# placa_v4.net
KiCad netlist of a schematic drawn in EAGLE
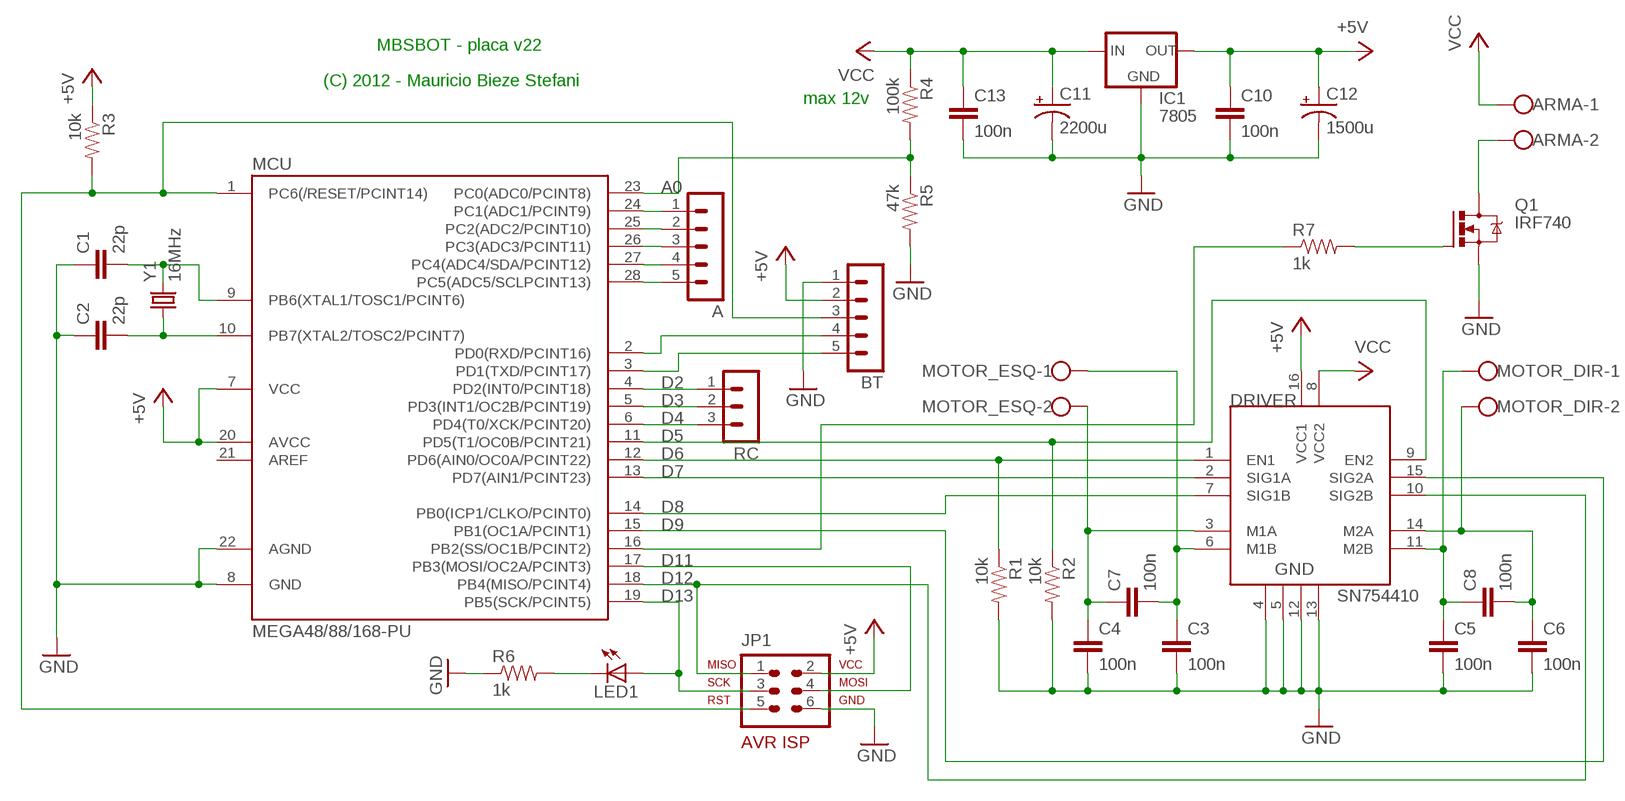
[diagram p0: schematic, sheet 1]

(export (version "E")
  (design (tool "Eeschema 10.0.6"))
  (components
    (comp (ref "A")
      (value "MA05-1")
      (footprint "eagle-import:MA05-1")
      (libsource (lib "eagle-import") (part "MA05-1"))
    )
    (comp (ref "ARMA")
      (value "W237-102")
      (footprint "eagle-import:W237-102")
      (fields (field (name "MPN") "237-102"))
      (libsource (lib "eagle-import") (part "W237-102"))
    )
    (comp (ref "BT")
      (value "MA05-1")
      (footprint "eagle-import:MA05-1")
      (libsource (lib "eagle-import") (part "MA05-1"))
    )
    (comp (ref "C1")
      (value "22p")
      (footprint "eagle-import:CAP-PTH-SMALL-KIT")
      (libsource (lib "eagle-import") (part "CAPKIT"))
    )
    (comp (ref "C2")
      (value "22p")
      (footprint "eagle-import:CAP-PTH-SMALL-KIT")
      (libsource (lib "eagle-import") (part "CAPKIT"))
    )
    (comp (ref "C3")
      (value "100n")
      (footprint "eagle-import:CAP-PTH-5MM")
      (libsource (lib "eagle-import") (part "CAPPTH1"))
    )
    (comp (ref "C4")
      (value "100n")
      (footprint "eagle-import:CAP-PTH-5MM")
      (libsource (lib "eagle-import") (part "CAPPTH1"))
    )
    (comp (ref "C5")
      (value "100n")
      (footprint "eagle-import:CAP-PTH-5MM")
      (libsource (lib "eagle-import") (part "CAPPTH1"))
    )
    (comp (ref "C6")
      (value "100n")
      (footprint "eagle-import:CAP-PTH-5MM")
      (libsource (lib "eagle-import") (part "CAPPTH1"))
    )
    (comp (ref "C7")
      (value "100n")
      (footprint "eagle-import:CAP-PTH-5MM")
      (libsource (lib "eagle-import") (part "CAPPTH1"))
    )
    (comp (ref "C8")
      (value "100n")
      (footprint "eagle-import:CAP-PTH-5MM")
      (libsource (lib "eagle-import") (part "CAPPTH1"))
    )
    (comp (ref "C10")
      (value "100n")
      (footprint "eagle-import:CAP-PTH-5MM")
      (libsource (lib "eagle-import") (part "CAPPTH1"))
    )
    (comp (ref "C11")
      (value "2200u")
      (footprint "eagle-import:CPOL-RADIAL-100UF-25V")
      (libsource (lib "eagle-import") (part "CAP_POLPTH1"))
    )
    (comp (ref "C12")
      (value "1500u")
      (footprint "eagle-import:CPOL-RADIAL-100UF-25V")
      (libsource (lib "eagle-import") (part "CAP_POLPTH1"))
    )
    (comp (ref "C13")
      (value "100n")
      (footprint "eagle-import:CAP-PTH-5MM")
      (libsource (lib "eagle-import") (part "CAPPTH1"))
    )
    (comp (ref "DRIVER")
      (value "SN754410")
      (footprint "eagle-import:DIP16")
      (libsource (lib "eagle-import") (part "SN754410"))
    )
    (comp (ref "IC1")
      (value "7805")
      (footprint "eagle-import:78XXS")
      (libsource (lib "eagle-import") (part "78XXS"))
    )
    (comp (ref "JP1")
      (value "AVR-ISP-6VERT")
      (footprint "eagle-import:AVR-ISP-6")
      (libsource (lib "eagle-import") (part "AVR-ISP-6VERT"))
    )
    (comp (ref "LED1")
      (value "LED3MM")
      (footprint "eagle-import:LED3MM")
      (libsource (lib "eagle-import") (part "LED3MM"))
    )
    (comp (ref "MCU")
      (value "MEGA48/88/168-PU")
      (footprint "eagle-import:DIL28-3")
      (libsource (lib "eagle-import") (part "MEGA48/88/168-PU"))
    )
    (comp (ref "MOTOR_DIR")
      (value "W237-102")
      (footprint "eagle-import:W237-102")
      (fields (field (name "MPN") "237-102"))
      (libsource (lib "eagle-import") (part "W237-102"))
    )
    (comp (ref "MOTOR_ESQ")
      (value "W237-102")
      (footprint "eagle-import:W237-102")
      (fields (field (name "MPN") "237-102"))
      (libsource (lib "eagle-import") (part "W237-102"))
    )
    (comp (ref "Q1")
      (value "IRF740")
      (footprint "eagle-import:TO220BV")
      (libsource (lib "eagle-import") (part "IRF740"))
    )
    (comp (ref "R1")
      (value "10k")
      (footprint "eagle-import:AXIAL-0.5")
      (libsource (lib "eagle-import") (part "RESISTORPTH-1/2W"))
    )
    (comp (ref "R2")
      (value "10k")
      (footprint "eagle-import:AXIAL-0.5")
      (libsource (lib "eagle-import") (part "RESISTORPTH-1/2W"))
    )
    (comp (ref "R3")
      (value "10k")
      (footprint "eagle-import:AXIAL-0.5")
      (libsource (lib "eagle-import") (part "RESISTORPTH-1/2W"))
    )
    (comp (ref "R4")
      (value "100k")
      (footprint "eagle-import:AXIAL-0.5")
      (libsource (lib "eagle-import") (part "RESISTORPTH-1/2W"))
    )
    (comp (ref "R5")
      (value "47k")
      (footprint "eagle-import:AXIAL-0.5")
      (libsource (lib "eagle-import") (part "RESISTORPTH-1/2W"))
    )
    (comp (ref "R6")
      (value "1k")
      (footprint "eagle-import:AXIAL-0.3-KIT")
      (libsource (lib "eagle-import") (part "RESISTORKIT"))
    )
    (comp (ref "R7")
      (value "1k")
      (footprint "eagle-import:AXIAL-0.3-KIT")
      (libsource (lib "eagle-import") (part "RESISTORKIT"))
    )
    (comp (ref "RC")
      (value "MA03-1")
      (footprint "eagle-import:MA03-1")
      (libsource (lib "eagle-import") (part "MA03-1"))
    )
    (comp (ref "Y1")
      (value "16MHz")
      (footprint "eagle-import:HC49US")
      (libsource (lib "eagle-import") (part "CRYSTALHC49US"))
    )
  )
  (nets
    (net (code "1") (name "+5V") (class "Default")
      (node (ref "BT") (pin "2") (pinfunction "2_2") (pintype "passive"))
      (node (ref "C10") (pin "1") (pinfunction "1_1") (pintype "passive"))
      (node (ref "C12") (pin "1") (pinfunction "+_1") (pintype "passive"))
      (node (ref "DRIVER") (pin "16") (pinfunction "VCC1_16") (pintype "power_in"))
      (node (ref "IC1") (pin "OUT") (pinfunction "OUT_OUT") (pintype "passive"))
      (node (ref "JP1") (pin "2") (pinfunction "2_2") (pintype "passive"))
      (node (ref "MCU") (pin "20") (pinfunction "AVCC_20") (pintype "passive"))
      (node (ref "MCU") (pin "7") (pinfunction "VCC_7") (pintype "power_in"))
      (node (ref "R3") (pin "P$1") (pinfunction "1_P$1") (pintype "passive"))
    )
    (net (code "2") (name "/A0") (class "Default")
      (node (ref "MCU") (pin "23") (pinfunction "PC0(ADC0/PCINT8)_23") (pintype "bidirectional"))
      (node (ref "R4") (pin "P$2") (pinfunction "2_P$2") (pintype "passive"))
      (node (ref "R5") (pin "P$1") (pinfunction "1_P$1") (pintype "passive"))
    )
    (net (code "3") (name "/D2") (class "Default")
      (node (ref "MCU") (pin "4") (pinfunction "PD2(INT0/PCINT18)_4") (pintype "bidirectional"))
      (node (ref "RC") (pin "1") (pinfunction "1_1") (pintype "passive"))
    )
    (net (code "4") (name "/D3") (class "Default")
      (node (ref "MCU") (pin "5") (pinfunction "PD3(INT1/OC2B/PCINT19)_5") (pintype "bidirectional"))
      (node (ref "RC") (pin "2") (pinfunction "2_2") (pintype "passive"))
    )
    (net (code "5") (name "/D4") (class "Default")
      (node (ref "MCU") (pin "6") (pinfunction "PD4(T0/XCK/PCINT20)_6") (pintype "bidirectional"))
      (node (ref "RC") (pin "3") (pinfunction "3_3") (pintype "passive"))
    )
    (net (code "6") (name "/D5") (class "Default")
      (node (ref "DRIVER") (pin "9") (pinfunction "EN2_9") (pintype "bidirectional"))
      (node (ref "MCU") (pin "11") (pinfunction "PD5(T1/OC0B/PCINT21)_11") (pintype "bidirectional"))
      (node (ref "R2") (pin "P$1") (pinfunction "1_P$1") (pintype "passive"))
    )
    (net (code "7") (name "/D6") (class "Default")
      (node (ref "DRIVER") (pin "1") (pinfunction "EN1_1") (pintype "bidirectional"))
      (node (ref "MCU") (pin "12") (pinfunction "PD6(AIN0/OC0A/PCINT22)_12") (pintype "bidirectional"))
      (node (ref "R1") (pin "P$1") (pinfunction "1_P$1") (pintype "passive"))
    )
    (net (code "8") (name "/D7") (class "Default")
      (node (ref "DRIVER") (pin "2") (pinfunction "SIG1A_2") (pintype "bidirectional"))
      (node (ref "MCU") (pin "13") (pinfunction "PD7(AIN1/PCINT23)_13") (pintype "bidirectional"))
    )
    (net (code "9") (name "/D8") (class "Default")
      (node (ref "DRIVER") (pin "7") (pinfunction "SIG1B_7") (pintype "bidirectional"))
      (node (ref "MCU") (pin "14") (pinfunction "PB0(ICP1/CLKO/PCINT0)_14") (pintype "bidirectional"))
    )
    (net (code "10") (name "/D9") (class "Default")
      (node (ref "DRIVER") (pin "15") (pinfunction "SIG2A_15") (pintype "bidirectional"))
      (node (ref "MCU") (pin "15") (pinfunction "PB1(OC1A/PCINT1)_15") (pintype "bidirectional"))
      (node (ref "MCU") (pin "16") (pinfunction "PB2(SS/OC1B/PCINT2)_16") (pintype "bidirectional"))
      (node (ref "R7") (pin "P$1") (pinfunction "1_P$1") (pintype "passive"))
    )
    (net (code "11") (name "/D11") (class "Default")
      (node (ref "JP1") (pin "4") (pinfunction "4_4") (pintype "passive"))
      (node (ref "MCU") (pin "17") (pinfunction "PB3(MOSI/OC2A/PCINT3)_17") (pintype "bidirectional"))
    )
    (net (code "12") (name "/D12") (class "Default")
      (node (ref "DRIVER") (pin "10") (pinfunction "SIG2B_10") (pintype "bidirectional"))
      (node (ref "JP1") (pin "1") (pinfunction "1_1") (pintype "passive"))
      (node (ref "MCU") (pin "18") (pinfunction "PB4(MISO/PCINT4)_18") (pintype "bidirectional"))
    )
    (net (code "13") (name "/D13") (class "Default")
      (node (ref "JP1") (pin "3") (pinfunction "3_3") (pintype "passive"))
      (node (ref "LED1") (pin "A") (pinfunction "A_A") (pintype "passive"))
      (node (ref "MCU") (pin "19") (pinfunction "PB5(SCK/PCINT5)_19") (pintype "bidirectional"))
    )
    (net (code "14") (name "GND") (class "Default")
      (node (ref "BT") (pin "1") (pinfunction "1_1") (pintype "passive"))
      (node (ref "C1") (pin "1") (pinfunction "1_1") (pintype "passive"))
      (node (ref "C10") (pin "2") (pinfunction "2_2") (pintype "passive"))
      (node (ref "C11") (pin "2") (pinfunction "-_2") (pintype "passive"))
      (node (ref "C12") (pin "2") (pinfunction "-_2") (pintype "passive"))
      (node (ref "C13") (pin "2") (pinfunction "2_2") (pintype "passive"))
      (node (ref "C2") (pin "1") (pinfunction "1_1") (pintype "passive"))
      (node (ref "C3") (pin "2") (pinfunction "2_2") (pintype "passive"))
      (node (ref "C4") (pin "2") (pinfunction "2_2") (pintype "passive"))
      (node (ref "C5") (pin "2") (pinfunction "2_2") (pintype "passive"))
      (node (ref "C6") (pin "2") (pinfunction "2_2") (pintype "passive"))
      (node (ref "DRIVER") (pin "12") (pinfunction "P12_12") (pintype "power_in"))
      (node (ref "DRIVER") (pin "13") (pinfunction "P13_13") (pintype "power_in"))
      (node (ref "DRIVER") (pin "4") (pinfunction "P4_4") (pintype "power_in"))
      (node (ref "DRIVER") (pin "5") (pinfunction "P5_5") (pintype "power_in"))
      (node (ref "IC1") (pin "GND") (pinfunction "GND_GND") (pintype "input"))
      (node (ref "JP1") (pin "6") (pinfunction "6_6") (pintype "passive"))
      (node (ref "MCU") (pin "22") (pinfunction "AGND_22") (pintype "power_in"))
      (node (ref "MCU") (pin "8") (pinfunction "GND_8") (pintype "power_in"))
      (node (ref "Q1") (pin "S") (pinfunction "S_S") (pintype "passive"))
      (node (ref "R1") (pin "P$2") (pinfunction "2_P$2") (pintype "passive"))
      (node (ref "R2") (pin "P$2") (pinfunction "2_P$2") (pintype "passive"))
      (node (ref "R5") (pin "P$2") (pinfunction "2_P$2") (pintype "passive"))
      (node (ref "R6") (pin "P$1") (pinfunction "1_P$1") (pintype "passive"))
    )
    (net (code "15") (name "Net-(ARMAB-KL)") (class "Default")
      (node (ref "ARMA") (pin "2") (pinfunction "KL_2") (pintype "passive"))
      (node (ref "Q1") (pin "D") (pinfunction "D_D") (pintype "passive"))
    )
    (net (code "16") (name "Net-(DRIVER-M1A)") (class "Default")
      (node (ref "C4") (pin "1") (pinfunction "1_1") (pintype "passive"))
      (node (ref "C7") (pin "1") (pinfunction "1_1") (pintype "passive"))
      (node (ref "DRIVER") (pin "3") (pinfunction "M1A_3") (pintype "bidirectional"))
      (node (ref "MOTOR_ESQ") (pin "2") (pinfunction "KL_2") (pintype "passive"))
    )
    (net (code "17") (name "Net-(DRIVER-M1B)") (class "Default")
      (node (ref "C3") (pin "1") (pinfunction "1_1") (pintype "passive"))
      (node (ref "C7") (pin "2") (pinfunction "2_2") (pintype "passive"))
      (node (ref "DRIVER") (pin "6") (pinfunction "M1B_6") (pintype "bidirectional"))
      (node (ref "MOTOR_ESQ") (pin "1") (pinfunction "KL_1") (pintype "passive"))
    )
    (net (code "18") (name "Net-(DRIVER-M2A)") (class "Default")
      (node (ref "C6") (pin "1") (pinfunction "1_1") (pintype "passive"))
      (node (ref "C8") (pin "2") (pinfunction "2_2") (pintype "passive"))
      (node (ref "DRIVER") (pin "14") (pinfunction "M2A_14") (pintype "bidirectional"))
      (node (ref "MOTOR_DIR") (pin "2") (pinfunction "KL_2") (pintype "passive"))
    )
    (net (code "19") (name "Net-(DRIVER-M2B)") (class "Default")
      (node (ref "C5") (pin "1") (pinfunction "1_1") (pintype "passive"))
      (node (ref "C8") (pin "1") (pinfunction "1_1") (pintype "passive"))
      (node (ref "DRIVER") (pin "11") (pinfunction "M2B_11") (pintype "bidirectional"))
      (node (ref "MOTOR_DIR") (pin "1") (pinfunction "KL_1") (pintype "passive"))
    )
    (net (code "20") (name "Net-(LED1-C)") (class "Default")
      (node (ref "LED1") (pin "K") (pinfunction "C_K") (pintype "passive"))
      (node (ref "R6") (pin "P$2") (pinfunction "2_P$2") (pintype "passive"))
    )
    (net (code "21") (name "Net-(MCU-PB6(XTAL1{slash}TOSC1{slash}PCINT6))") (class "Default")
      (node (ref "C1") (pin "2") (pinfunction "2_2") (pintype "passive"))
      (node (ref "MCU") (pin "9") (pinfunction "PB6(XTAL1/TOSC1/PCINT6)_9") (pintype "bidirectional"))
      (node (ref "Y1") (pin "2") (pinfunction "2_2") (pintype "passive"))
    )
    (net (code "22") (name "Net-(MCU-PB7(XTAL2{slash}TOSC2{slash}PCINT7))") (class "Default")
      (node (ref "C2") (pin "2") (pinfunction "2_2") (pintype "passive"))
      (node (ref "MCU") (pin "10") (pinfunction "PB7(XTAL2/TOSC2/PCINT7)_10") (pintype "bidirectional"))
      (node (ref "Y1") (pin "1") (pinfunction "1_1") (pintype "passive"))
    )
    (net (code "23") (name "Net-(MCU-PC1(ADC1{slash}PCINT9))") (class "Default")
      (node (ref "A") (pin "1") (pinfunction "1_1") (pintype "passive"))
      (node (ref "MCU") (pin "24") (pinfunction "PC1(ADC1/PCINT9)_24") (pintype "bidirectional"))
    )
    (net (code "24") (name "Net-(MCU-PC2(ADC2{slash}PCINT10))") (class "Default")
      (node (ref "A") (pin "2") (pinfunction "2_2") (pintype "passive"))
      (node (ref "MCU") (pin "25") (pinfunction "PC2(ADC2/PCINT10)_25") (pintype "bidirectional"))
    )
    (net (code "25") (name "Net-(MCU-PC3(ADC3{slash}PCINT11))") (class "Default")
      (node (ref "A") (pin "3") (pinfunction "3_3") (pintype "passive"))
      (node (ref "MCU") (pin "26") (pinfunction "PC3(ADC3/PCINT11)_26") (pintype "bidirectional"))
    )
    (net (code "26") (name "Net-(MCU-PC4(ADC4{slash}SDA{slash}PCINT12))") (class "Default")
      (node (ref "A") (pin "4") (pinfunction "4_4") (pintype "passive"))
      (node (ref "MCU") (pin "27") (pinfunction "PC4(ADC4/SDA/PCINT12)_27") (pintype "bidirectional"))
    )
    (net (code "27") (name "Net-(MCU-PC5(ADC5{slash}SCLPCINT13))") (class "Default")
      (node (ref "A") (pin "5") (pinfunction "5_5") (pintype "passive"))
      (node (ref "MCU") (pin "28") (pinfunction "PC5(ADC5/SCLPCINT13)_28") (pintype "bidirectional"))
    )
    (net (code "28") (name "Net-(MCU-PC6({slash}RESET{slash}PCINT14))") (class "Default")
      (node (ref "BT") (pin "3") (pinfunction "3_3") (pintype "passive"))
      (node (ref "JP1") (pin "5") (pinfunction "5_5") (pintype "passive"))
      (node (ref "MCU") (pin "1") (pinfunction "PC6(/RESET/PCINT14)_1") (pintype "bidirectional"))
      (node (ref "R3") (pin "P$2") (pinfunction "2_P$2") (pintype "passive"))
    )
    (net (code "29") (name "Net-(MCU-PD0(RXD{slash}PCINT16))") (class "Default")
      (node (ref "BT") (pin "4") (pinfunction "4_4") (pintype "passive"))
      (node (ref "MCU") (pin "2") (pinfunction "PD0(RXD/PCINT16)_2") (pintype "bidirectional"))
    )
    (net (code "30") (name "Net-(MCU-PD1(TXD{slash}PCINT17))") (class "Default")
      (node (ref "BT") (pin "5") (pinfunction "5_5") (pintype "passive"))
      (node (ref "MCU") (pin "3") (pinfunction "PD1(TXD/PCINT17)_3") (pintype "bidirectional"))
    )
    (net (code "31") (name "Net-(R7-2)") (class "Default")
      (node (ref "Q1") (pin "G") (pinfunction "G_G") (pintype "passive"))
      (node (ref "R7") (pin "P$2") (pinfunction "2_P$2") (pintype "passive"))
    )
    (net (code "32") (name "VCC") (class "Default")
      (node (ref "ARMA") (pin "1") (pinfunction "KL_1") (pintype "passive"))
      (node (ref "C11") (pin "1") (pinfunction "+_1") (pintype "passive"))
      (node (ref "C13") (pin "1") (pinfunction "1_1") (pintype "passive"))
      (node (ref "DRIVER") (pin "8") (pinfunction "VCC2_8") (pintype "power_in"))
      (node (ref "IC1") (pin "IN") (pinfunction "IN_IN") (pintype "input"))
      (node (ref "R4") (pin "P$1") (pinfunction "1_P$1") (pintype "passive"))
    )
    (net (code "33") (name "unconnected-(MCU-AREF-Pad21)") (class "Default")
      (node (ref "MCU") (pin "21") (pinfunction "AREF_21") (pintype "passive"))
    )
  )
)
